# Laptimer.net
KiCad netlist of a schematic drawn in EAGLE
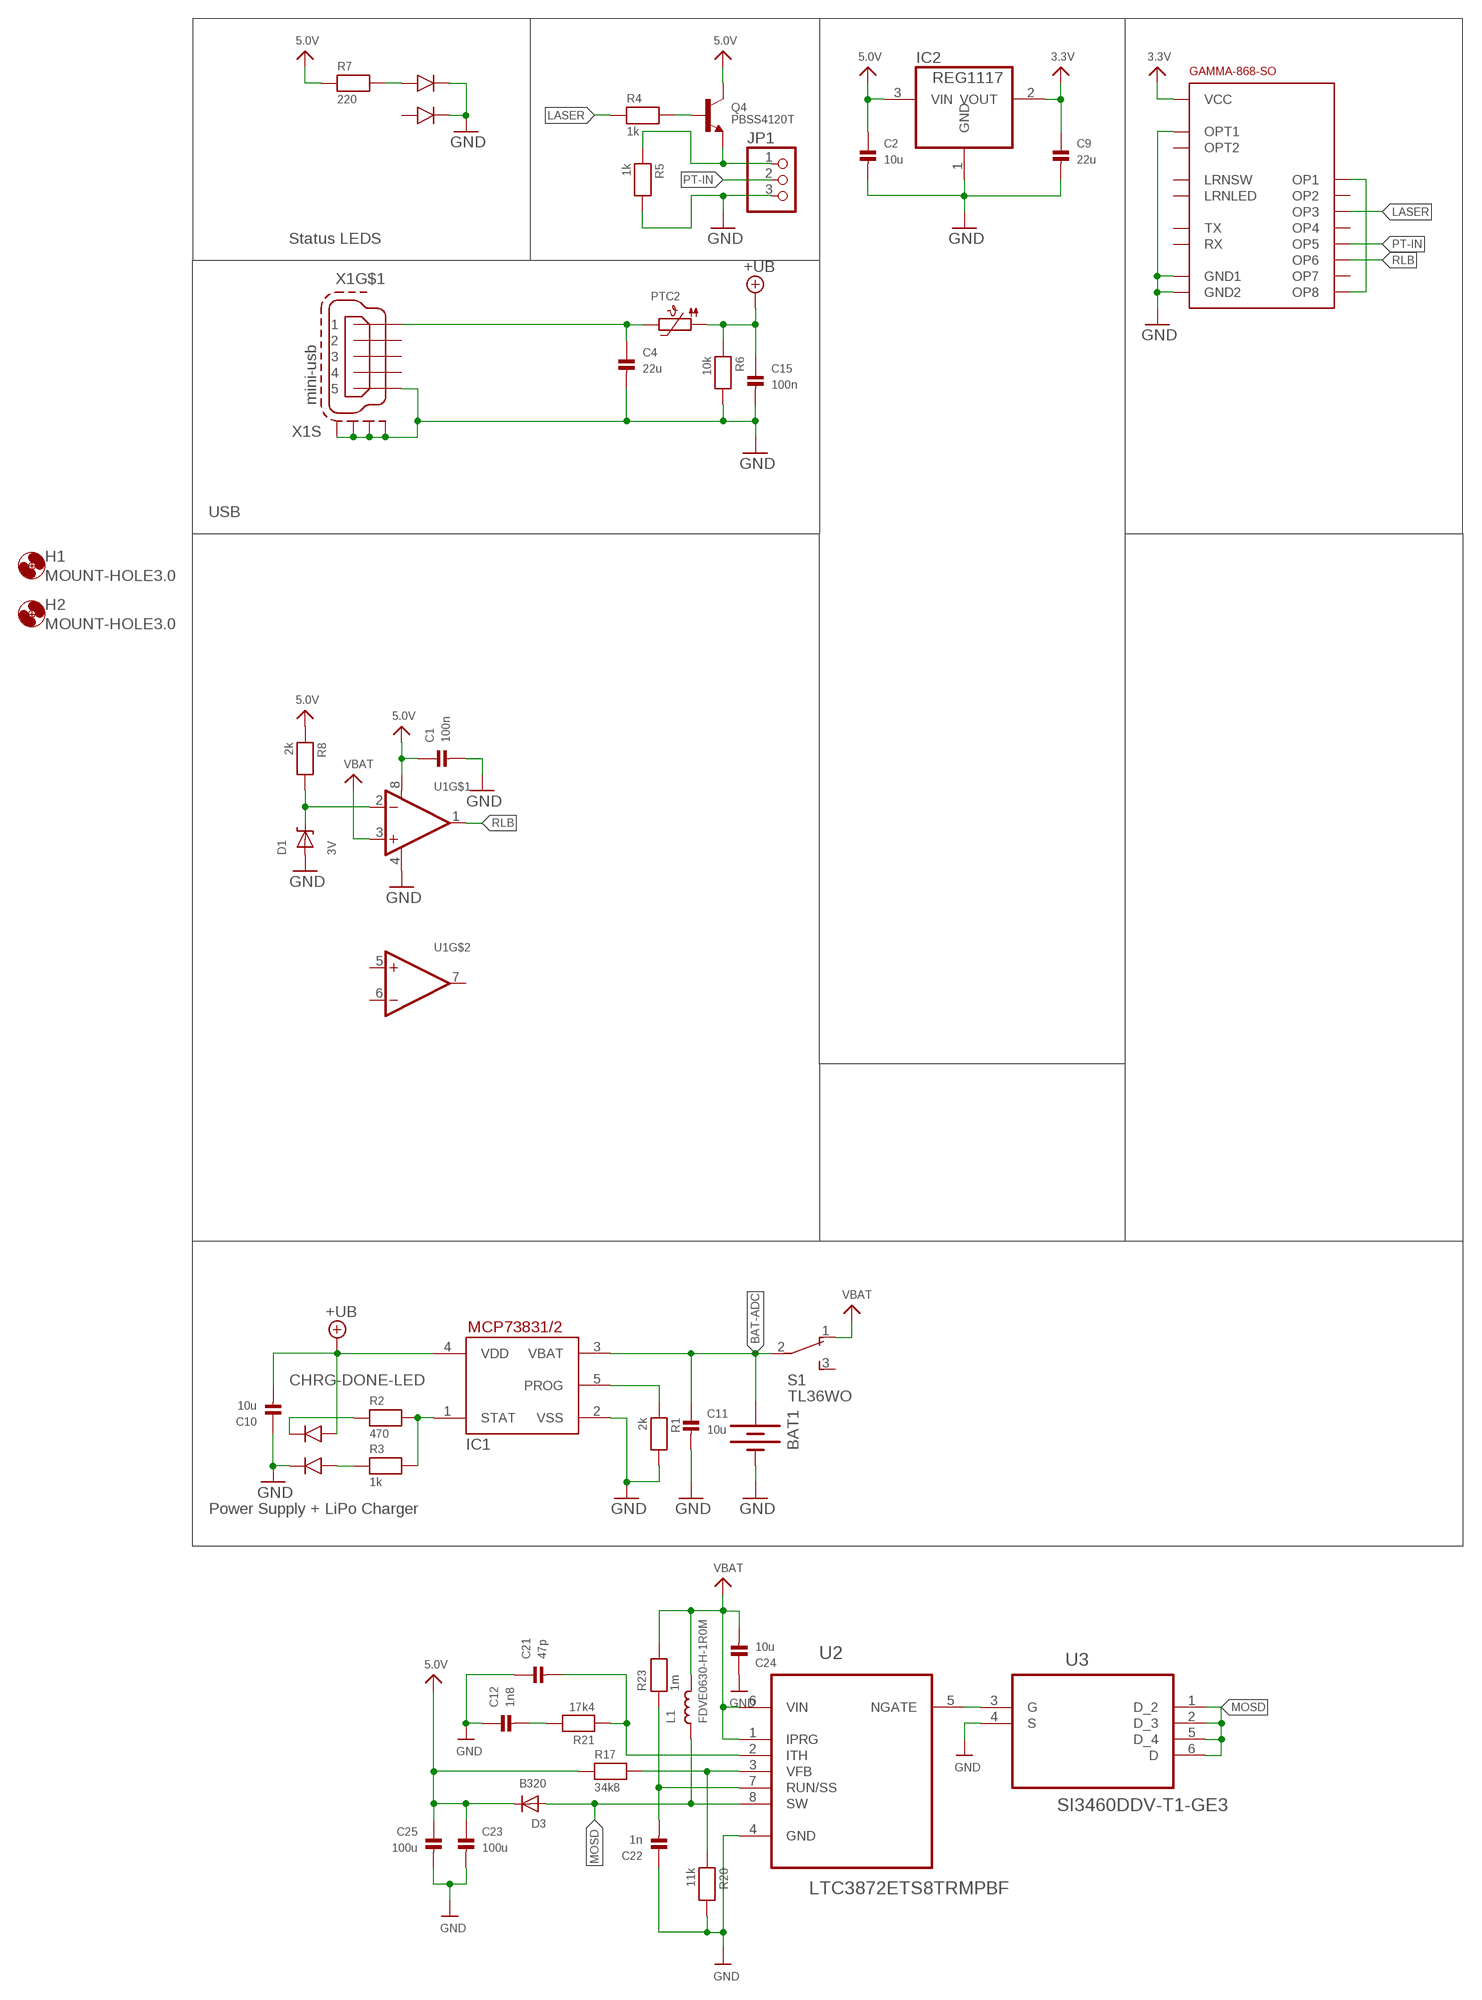
[diagram p0: schematic, sheet 1]

(export (version "E")
  (design (tool "Eeschema 10.0.6"))
  (components
    (comp (ref "BAT1")
      (value "BATTERY18650")
      (footprint "eagle-import:BATTERY_18650-HOLDER")
      (libsource (lib "eagle-import") (part "BATTERY18650"))
    )
    (comp (ref "C1")
      (value "100n")
      (footprint "eagle-import:_0603")
      (libsource (lib "eagle-import") (part "CAP_CERAMIC_0603"))
    )
    (comp (ref "C2")
      (value "10u")
      (footprint "eagle-import:_0805")
      (libsource (lib "eagle-import") (part "CAP_CERAMIC_0805"))
    )
    (comp (ref "C4")
      (value "22u")
      (footprint "eagle-import:_0805")
      (libsource (lib "eagle-import") (part "CAP_CERAMIC_0805"))
    )
    (comp (ref "C9")
      (value "22u")
      (footprint "eagle-import:_0805")
      (libsource (lib "eagle-import") (part "CAP_CERAMIC_0805"))
    )
    (comp (ref "C10")
      (value "10u")
      (footprint "eagle-import:_0805")
      (libsource (lib "eagle-import") (part "CAP_CERAMIC_0805"))
    )
    (comp (ref "C11")
      (value "10u")
      (footprint "eagle-import:_0805")
      (libsource (lib "eagle-import") (part "CAP_CERAMIC_0805"))
    )
    (comp (ref "C12")
      (value "1n8")
      (footprint "eagle-import:_0603")
      (libsource (lib "eagle-import") (part "CAP_CERAMIC_0603"))
    )
    (comp (ref "C15")
      (value "100n")
      (footprint "eagle-import:_0603")
      (libsource (lib "eagle-import") (part "CAP_CERAMIC_0603"))
    )
    (comp (ref "C21")
      (value "47p")
      (footprint "eagle-import:_0603")
      (libsource (lib "eagle-import") (part "CAP_CERAMIC_0603"))
    )
    (comp (ref "C22")
      (value "1n")
      (footprint "eagle-import:_0603")
      (libsource (lib "eagle-import") (part "CAP_CERAMIC_0603"))
    )
    (comp (ref "C23")
      (value "100u")
      (footprint "eagle-import:1206")
      (libsource (lib "eagle-import") (part "CAP_CERAMIC1206"))
    )
    (comp (ref "C24")
      (value "10u")
      (footprint "eagle-import:_0805")
      (libsource (lib "eagle-import") (part "CAP_CERAMIC_0805"))
    )
    (comp (ref "C25")
      (value "100u")
      (footprint "eagle-import:1206")
      (libsource (lib "eagle-import") (part "CAP_CERAMIC1206"))
    )
    (comp (ref "D1")
      (value "3V")
      (footprint "eagle-import:SMADIODE")
      (libsource (lib "eagle-import") (part "DIODE-ZENER"))
    )
    (comp (ref "D3")
      (value "B320")
      (footprint "eagle-import:SMADIODE")
      (libsource (lib "eagle-import") (part "DIODESMA"))
    )
    (comp (ref "H1")
      (value "MOUNT-HOLE3.0")
      (footprint "eagle-import:3,0")
      (libsource (lib "eagle-import") (part "MOUNT-HOLE3.0"))
    )
    (comp (ref "H2")
      (value "MOUNT-HOLE3.0")
      (footprint "eagle-import:3,0")
      (libsource (lib "eagle-import") (part "MOUNT-HOLE3.0"))
    )
    (comp (ref "IC1")
      (value "MCP73831/OT")
      (footprint "eagle-import:SOT23-5L")
      (libsource (lib "eagle-import") (part "MCP73831/OT"))
    )
    (comp (ref "IC2")
      (value "REG1117")
      (footprint "eagle-import:SOT223")
      (libsource (lib "eagle-import") (part "REG1117"))
    )
    (comp (ref "JP1")
      (value "PINHD-1X3")
      (footprint "eagle-import:1X03")
      (libsource (lib "eagle-import") (part "PINHD-1X3"))
    )
    (comp (ref "L1")
      (value "FDVE0630-H-1R0M")
      (footprint "eagle-import:INDUCTOR_6X6MM_TDK_SLF6045")
      (libsource (lib "eagle-import") (part "INDUCTORTDK_SLF6045"))
    )
    (comp (ref "PTC2")
      (value "PTC1206")
      (footprint "eagle-import:1206")
      (libsource (lib "eagle-import") (part "PTC1206"))
    )
    (comp (ref "Q4")
      (value "PBSS4120T")
      (footprint "eagle-import:SOT23-WIDE")
      (libsource (lib "eagle-import") (part "TRANSISTOR_NPNWIDE"))
    )
    (comp (ref "R1")
      (value "2k")
      (footprint "eagle-import:_0603")
      (libsource (lib "eagle-import") (part "RESISTOR_0603"))
    )
    (comp (ref "R2")
      (value "470")
      (footprint "eagle-import:_0603")
      (libsource (lib "eagle-import") (part "RESISTOR_0603"))
    )
    (comp (ref "R3")
      (value "1k")
      (footprint "eagle-import:_0603")
      (libsource (lib "eagle-import") (part "RESISTOR_0603"))
    )
    (comp (ref "R4")
      (value "1k")
      (footprint "eagle-import:_0603")
      (libsource (lib "eagle-import") (part "RESISTOR_0603"))
    )
    (comp (ref "R5")
      (value "1k")
      (footprint "eagle-import:_0603")
      (libsource (lib "eagle-import") (part "RESISTOR_0603"))
    )
    (comp (ref "R6")
      (value "10k")
      (footprint "eagle-import:_0603")
      (libsource (lib "eagle-import") (part "RESISTOR_0603"))
    )
    (comp (ref "R7")
      (value "220")
      (footprint "eagle-import:_0603")
      (libsource (lib "eagle-import") (part "RESISTOR_0603"))
    )
    (comp (ref "R8")
      (value "2k")
      (footprint "eagle-import:_0603")
      (libsource (lib "eagle-import") (part "RESISTOR_0603"))
    )
    (comp (ref "R17")
      (value "34k8")
      (footprint "eagle-import:_0603")
      (libsource (lib "eagle-import") (part "RESISTOR_0603"))
    )
    (comp (ref "R20")
      (value "11k")
      (footprint "eagle-import:_0603")
      (libsource (lib "eagle-import") (part "RESISTOR_0603"))
    )
    (comp (ref "R21")
      (value "17k4")
      (footprint "eagle-import:_0603")
      (libsource (lib "eagle-import") (part "RESISTOR_0603"))
    )
    (comp (ref "R23")
      (value "1m")
      (footprint "eagle-import:_0603")
      (libsource (lib "eagle-import") (part "RESISTOR_0603"))
    )
    (comp (ref "S1")
      (value "TL36WO")
      (footprint "eagle-import:TL3XWO")
      (libsource (lib "eagle-import") (part "TL36WO"))
    )
    (comp (ref "U$7")
      (value "GAMMA-868-SO")
      (footprint "eagle-import:UNICORN_V2_GAMMA-868-SO")
      (libsource (lib "eagle-import") (part "GAMMA-868-SO"))
    )
    (comp (ref "U$13")
      (value "BI-LEVEL-LED-INDICATOR")
      (footprint "eagle-import:BI-LEVEL-LED-INDICATOR")
      (libsource (lib "eagle-import") (part "BI-LEVEL-LED-INDICATOR"))
    )
    (comp (ref "U$14")
      (value "BI-LEVEL-LED-INDICATOR")
      (footprint "eagle-import:BI-LEVEL-LED-INDICATOR")
      (libsource (lib "eagle-import") (part "BI-LEVEL-LED-INDICATOR"))
    )
    (comp (ref "U1")
      (value "LM358")
      (footprint "eagle-import:SOIC8_150MIL")
      (libsource (lib "eagle-import") (part "LM358"))
    )
    (comp (ref "U2")
      (value "LTC3872ETS8TRMPBF")
      (footprint "eagle-import:SOT65P280X100-8N")
      (fields (field (name "MPN") "LTC3872ETS8#TRMPBF"))
      (libsource (lib "eagle-import") (part "LTC3872ETS8TRMPBF"))
    )
    (comp (ref "U3")
      (value "SI3460DDV-T1-GE3")
      (footprint "eagle-import:SOT95P285X110-6N")
      (fields (field (name "MPN") "SI3457CDV-T1-GE3"))
      (libsource (lib "eagle-import") (part "SI3457CDV-T1-GE3"))
    )
    (comp (ref "X1")
      (value "mini-usb")
      (footprint "eagle-import:32005-301")
      (libsource (lib "eagle-import") (part "MINI-USB-SCHIELD-32005-301"))
    )
  )
  (nets
    (net (code "1") (name "+UB") (class "Default")
      (node (ref "C10") (pin "2") (pinfunction "P$2_2") (pintype "passive"))
      (node (ref "C15") (pin "1") (pinfunction "P$1_1") (pintype "passive"))
      (node (ref "IC1") (pin "4") (pinfunction "VDD_4") (pintype "power_in"))
      (node (ref "PTC2") (pin "1") (pinfunction "1_1") (pintype "passive"))
      (node (ref "R6") (pin "1") (pinfunction "1_1") (pintype "passive"))
      (node (ref "U$13") (pin "ANODE1") (pinfunction "ANODE1_ANODE1") (pintype "bidirectional"))
    )
    (net (code "2") (name "/CHRG-DONE-LED") (class "Default")
      (node (ref "R3") (pin "1") (pinfunction "1_1") (pintype "passive"))
      (node (ref "U$13") (pin "ANODE2") (pinfunction "ANODE2_ANODE2") (pintype "bidirectional"))
    )
    (net (code "3") (name "3.3V") (class "Default")
      (node (ref "C9") (pin "1") (pinfunction "P$1_1") (pintype "passive"))
      (node (ref "IC2") (pin "2") (pinfunction "VOUT_2") (pintype "output"))
      (node (ref "U$7") (pin "P$16") (pinfunction "VCC_P$16") (pintype "bidirectional"))
    )
    (net (code "4") (name "5.0V") (class "Default")
      (node (ref "C1") (pin "1") (pinfunction "P$1_1") (pintype "passive"))
      (node (ref "C2") (pin "1") (pinfunction "P$1_1") (pintype "passive"))
      (node (ref "C23") (pin "1") (pinfunction "P$1_1") (pintype "passive"))
      (node (ref "C25") (pin "1") (pinfunction "P$1_1") (pintype "passive"))
      (node (ref "D3") (pin "C") (pinfunction "C_C") (pintype "passive"))
      (node (ref "IC2") (pin "3") (pinfunction "VIN_3") (pintype "input"))
      (node (ref "Q4") (pin "3") (pinfunction "C_3") (pintype "passive"))
      (node (ref "R17") (pin "1") (pinfunction "1_1") (pintype "passive"))
      (node (ref "R7") (pin "1") (pinfunction "1_1") (pintype "passive"))
      (node (ref "R8") (pin "1") (pinfunction "1_1") (pintype "passive"))
      (node (ref "U1") (pin "8") (pinfunction "V+_8") (pintype "power_in"))
    )
    (net (code "5") (name "BAT-ADC") (class "Default")
      (node (ref "BAT1") (pin "PWR@1") (pinfunction "+_PWR@1") (pintype "power_in"))
      (node (ref "C11") (pin "1") (pinfunction "P$1_1") (pintype "passive"))
      (node (ref "IC1") (pin "3") (pinfunction "VBAT_3") (pintype "bidirectional"))
      (node (ref "S1") (pin "2") (pinfunction "P_2") (pintype "passive"))
    )
    (net (code "6") (name "GND") (class "Default")
      (node (ref "BAT1") (pin "GND@1") (pinfunction "-_GND@1") (pintype "power_in"))
      (node (ref "C1") (pin "2") (pinfunction "P$2_2") (pintype "passive"))
      (node (ref "C10") (pin "1") (pinfunction "P$1_1") (pintype "passive"))
      (node (ref "C11") (pin "2") (pinfunction "P$2_2") (pintype "passive"))
      (node (ref "C12") (pin "1") (pinfunction "P$1_1") (pintype "passive"))
      (node (ref "C15") (pin "2") (pinfunction "P$2_2") (pintype "passive"))
      (node (ref "C2") (pin "2") (pinfunction "P$2_2") (pintype "passive"))
      (node (ref "C21") (pin "1") (pinfunction "P$1_1") (pintype "passive"))
      (node (ref "C22") (pin "1") (pinfunction "P$1_1") (pintype "passive"))
      (node (ref "C23") (pin "2") (pinfunction "P$2_2") (pintype "passive"))
      (node (ref "C24") (pin "1") (pinfunction "P$1_1") (pintype "passive"))
      (node (ref "C25") (pin "2") (pinfunction "P$2_2") (pintype "passive"))
      (node (ref "C4") (pin "2") (pinfunction "P$2_2") (pintype "passive"))
      (node (ref "C9") (pin "2") (pinfunction "P$2_2") (pintype "passive"))
      (node (ref "D1") (pin "A") (pinfunction "A_A") (pintype "passive"))
      (node (ref "IC1") (pin "2") (pinfunction "VSS_2") (pintype "power_in"))
      (node (ref "IC2") (pin "1") (pinfunction "GND_1") (pintype "power_in"))
      (node (ref "JP1") (pin "3") (pinfunction "3_3") (pintype "passive"))
      (node (ref "R1") (pin "2") (pinfunction "2_2") (pintype "passive"))
      (node (ref "R20") (pin "2") (pinfunction "2_2") (pintype "passive"))
      (node (ref "R5") (pin "2") (pinfunction "2_2") (pintype "passive"))
      (node (ref "R6") (pin "2") (pinfunction "2_2") (pintype "passive"))
      (node (ref "U$13") (pin "CATHODE2") (pinfunction "CATHODE2_CATHODE2") (pintype "bidirectional"))
      (node (ref "U$14") (pin "CATHODE1") (pinfunction "CATHODE1_CATHODE1") (pintype "bidirectional"))
      (node (ref "U$14") (pin "CATHODE2") (pinfunction "CATHODE2_CATHODE2") (pintype "bidirectional"))
      (node (ref "U$7") (pin "P$10") (pinfunction "OPT1_P$10") (pintype "bidirectional"))
      (node (ref "U$7") (pin "P$15") (pinfunction "GND2_P$15") (pintype "bidirectional"))
      (node (ref "U$7") (pin "P$2") (pinfunction "GND1_P$2") (pintype "bidirectional"))
      (node (ref "U1") (pin "4") (pinfunction "V-_4") (pintype "power_in"))
      (node (ref "U2") (pin "4") (pinfunction "GND_4") (pintype "passive"))
      (node (ref "U3") (pin "4") (pinfunction "S_4") (pintype "passive"))
      (node (ref "X1") (pin "5") (pinfunction "5_5") (pintype "passive"))
      (node (ref "X1") (pin "M1") (pinfunction "S1_M1") (pintype "passive"))
      (node (ref "X1") (pin "M2") (pinfunction "S2_M2") (pintype "passive"))
      (node (ref "X1") (pin "M3") (pinfunction "S3_M3") (pintype "passive"))
      (node (ref "X1") (pin "M4") (pinfunction "S4_M4") (pintype "passive"))
    )
    (net (code "7") (name "LASER") (class "Default")
      (node (ref "R4") (pin "1") (pinfunction "1_1") (pintype "passive"))
      (node (ref "U$7") (pin "P$7") (pinfunction "OP3_P$7") (pintype "bidirectional"))
    )
    (net (code "8") (name "MOSD") (class "Default")
      (node (ref "D3") (pin "A") (pinfunction "A_A") (pintype "passive"))
      (node (ref "L1") (pin "P$1") (pinfunction "1_P$1") (pintype "passive"))
      (node (ref "U2") (pin "8") (pinfunction "SW_8") (pintype "passive"))
      (node (ref "U3") (pin "1") (pinfunction "D_2_1") (pintype "passive"))
      (node (ref "U3") (pin "2") (pinfunction "D_3_2") (pintype "passive"))
      (node (ref "U3") (pin "5") (pinfunction "D_4_5") (pintype "passive"))
      (node (ref "U3") (pin "6") (pinfunction "D_6") (pintype "passive"))
    )
    (net (code "9") (name "Net-(C4-P$1)") (class "Default")
      (node (ref "C4") (pin "1") (pinfunction "P$1_1") (pintype "passive"))
      (node (ref "PTC2") (pin "2") (pinfunction "2_2") (pintype "passive"))
      (node (ref "X1") (pin "1") (pinfunction "1_1") (pintype "passive"))
    )
    (net (code "10") (name "Net-(C12-P$2)") (class "Default")
      (node (ref "C12") (pin "2") (pinfunction "P$2_2") (pintype "passive"))
      (node (ref "R21") (pin "2") (pinfunction "2_2") (pintype "passive"))
    )
    (net (code "11") (name "Net-(C21-P$2)") (class "Default")
      (node (ref "C21") (pin "2") (pinfunction "P$2_2") (pintype "passive"))
      (node (ref "R21") (pin "1") (pinfunction "1_1") (pintype "passive"))
      (node (ref "U2") (pin "2") (pinfunction "ITH_2") (pintype "input"))
    )
    (net (code "12") (name "Net-(C22-P$2)") (class "Default")
      (node (ref "C22") (pin "2") (pinfunction "P$2_2") (pintype "passive"))
      (node (ref "R23") (pin "1") (pinfunction "1_1") (pintype "passive"))
      (node (ref "U2") (pin "7") (pinfunction "RUN/SS_7") (pintype "input"))
    )
    (net (code "13") (name "Net-(IC1-PROG)") (class "Default")
      (node (ref "IC1") (pin "5") (pinfunction "PROG_5") (pintype "input"))
      (node (ref "R1") (pin "1") (pinfunction "1_1") (pintype "passive"))
    )
    (net (code "14") (name "Net-(IC1-STAT)") (class "Default")
      (node (ref "IC1") (pin "1") (pinfunction "STAT_1") (pintype "output"))
      (node (ref "R2") (pin "2") (pinfunction "2_2") (pintype "passive"))
      (node (ref "R3") (pin "2") (pinfunction "2_2") (pintype "passive"))
    )
    (net (code "15") (name "Net-(Q4-B)") (class "Default")
      (node (ref "Q4") (pin "1") (pinfunction "B_1") (pintype "passive"))
      (node (ref "R4") (pin "2") (pinfunction "2_2") (pintype "passive"))
    )
    (net (code "16") (name "Net-(Q4-E)") (class "Default")
      (node (ref "JP1") (pin "1") (pinfunction "1_1") (pintype "passive"))
      (node (ref "Q4") (pin "2") (pinfunction "E_2") (pintype "passive"))
      (node (ref "R5") (pin "1") (pinfunction "1_1") (pintype "passive"))
    )
    (net (code "17") (name "Net-(R2-Pad1)") (class "Default")
      (node (ref "R2") (pin "1") (pinfunction "1_1") (pintype "passive"))
      (node (ref "U$13") (pin "CATHODE1") (pinfunction "CATHODE1_CATHODE1") (pintype "bidirectional"))
    )
    (net (code "18") (name "Net-(R7-Pad2)") (class "Default")
      (node (ref "R7") (pin "2") (pinfunction "2_2") (pintype "passive"))
      (node (ref "U$14") (pin "ANODE2") (pinfunction "ANODE2_ANODE2") (pintype "bidirectional"))
    )
    (net (code "19") (name "Net-(U$7-OP1)") (class "Default")
      (node (ref "U$7") (pin "P$13") (pinfunction "OP8_P$13") (pintype "bidirectional"))
      (node (ref "U$7") (pin "P$3") (pinfunction "OP1_P$3") (pintype "bidirectional"))
    )
    (net (code "20") (name "Net-(U1A--IN)") (class "Default")
      (node (ref "D1") (pin "C") (pinfunction "C_C") (pintype "passive"))
      (node (ref "R8") (pin "2") (pinfunction "2_2") (pintype "passive"))
      (node (ref "U1") (pin "2") (pinfunction "-IN_2") (pintype "input"))
    )
    (net (code "21") (name "Net-(U2-NGATE)") (class "Default")
      (node (ref "U2") (pin "5") (pinfunction "NGATE_5") (pintype "output"))
      (node (ref "U3") (pin "3") (pinfunction "G_3") (pintype "passive"))
    )
    (net (code "22") (name "Net-(U2-VFB)") (class "Default")
      (node (ref "R17") (pin "2") (pinfunction "2_2") (pintype "passive"))
      (node (ref "R20") (pin "1") (pinfunction "1_1") (pintype "passive"))
      (node (ref "U2") (pin "3") (pinfunction "VFB_3") (pintype "input"))
    )
    (net (code "23") (name "PT-IN") (class "Default")
      (node (ref "JP1") (pin "2") (pinfunction "2_2") (pintype "passive"))
      (node (ref "U$7") (pin "P$9") (pinfunction "OP5_P$9") (pintype "bidirectional"))
    )
    (net (code "24") (name "RLB") (class "Default")
      (node (ref "U$7") (pin "P$11") (pinfunction "OP6_P$11") (pintype "bidirectional"))
      (node (ref "U1") (pin "1") (pinfunction "OUT_1") (pintype "output"))
    )
    (net (code "25") (name "VBAT") (class "Default")
      (node (ref "C24") (pin "2") (pinfunction "P$2_2") (pintype "passive"))
      (node (ref "L1") (pin "P$2") (pinfunction "2_P$2") (pintype "passive"))
      (node (ref "R23") (pin "2") (pinfunction "2_2") (pintype "passive"))
      (node (ref "S1") (pin "1") (pinfunction "O_1") (pintype "passive"))
      (node (ref "U1") (pin "3") (pinfunction "+IN_3") (pintype "input"))
      (node (ref "U2") (pin "1") (pinfunction "IPRG_1") (pintype "input"))
      (node (ref "U2") (pin "6") (pinfunction "VIN_6") (pintype "power_in"))
    )
    (net (code "26") (name "unconnected-(S1-S-Pad3)") (class "Default")
      (node (ref "S1") (pin "3") (pinfunction "S_3") (pintype "passive"))
    )
    (net (code "27") (name "unconnected-(U$7-LRNLED-PadP$6)") (class "Default")
      (node (ref "U$7") (pin "P$6") (pinfunction "LRNLED_P$6") (pintype "bidirectional"))
    )
    (net (code "28") (name "unconnected-(U$7-LRNSW-PadP$5)") (class "Default")
      (node (ref "U$7") (pin "P$5") (pinfunction "LRNSW_P$5") (pintype "bidirectional"))
    )
    (net (code "29") (name "unconnected-(U$7-OP2-PadP$4)") (class "Default")
      (node (ref "U$7") (pin "P$4") (pinfunction "OP2_P$4") (pintype "bidirectional"))
    )
    (net (code "30") (name "unconnected-(U$7-OP4-PadP$8)") (class "Default")
      (node (ref "U$7") (pin "P$8") (pinfunction "OP4_P$8") (pintype "bidirectional"))
    )
    (net (code "31") (name "unconnected-(U$7-OP7-PadP$12)") (class "Default")
      (node (ref "U$7") (pin "P$12") (pinfunction "OP7_P$12") (pintype "bidirectional"))
    )
    (net (code "32") (name "unconnected-(U$7-OPT2-PadP$14)") (class "Default")
      (node (ref "U$7") (pin "P$14") (pinfunction "OPT2_P$14") (pintype "bidirectional"))
    )
    (net (code "33") (name "unconnected-(U$7-RX-PadP$18)") (class "Default")
      (node (ref "U$7") (pin "P$18") (pinfunction "RX_P$18") (pintype "bidirectional"))
    )
    (net (code "34") (name "unconnected-(U$7-TX-PadP$17)") (class "Default")
      (node (ref "U$7") (pin "P$17") (pinfunction "TX_P$17") (pintype "bidirectional"))
    )
    (net (code "35") (name "unconnected-(U$14-PadANODE1)") (class "Default")
      (node (ref "U$14") (pin "ANODE1") (pinfunction "ANODE1_ANODE1") (pintype "bidirectional"))
    )
    (net (code "36") (name "unconnected-(U1B-+IN-Pad5)") (class "Default")
      (node (ref "U1") (pin "5") (pinfunction "+IN_5") (pintype "input"))
    )
    (net (code "37") (name "unconnected-(U1B--IN-Pad6)") (class "Default")
      (node (ref "U1") (pin "6") (pinfunction "-IN_6") (pintype "input"))
    )
    (net (code "38") (name "unconnected-(U1B-OUT-Pad7)") (class "Default")
      (node (ref "U1") (pin "7") (pinfunction "OUT_7") (pintype "output"))
    )
    (net (code "39") (name "unconnected-(X1-Pad2)") (class "Default")
      (node (ref "X1") (pin "2") (pinfunction "2_2") (pintype "passive"))
    )
    (net (code "40") (name "unconnected-(X1-Pad3)") (class "Default")
      (node (ref "X1") (pin "3") (pinfunction "3_3") (pintype "passive"))
    )
    (net (code "41") (name "unconnected-(X1-Pad4)") (class "Default")
      (node (ref "X1") (pin "4") (pinfunction "4_4") (pintype "passive"))
    )
  )
)
